# THAPMU__1_0.net
KiCad netlist of a schematic drawn in EAGLE
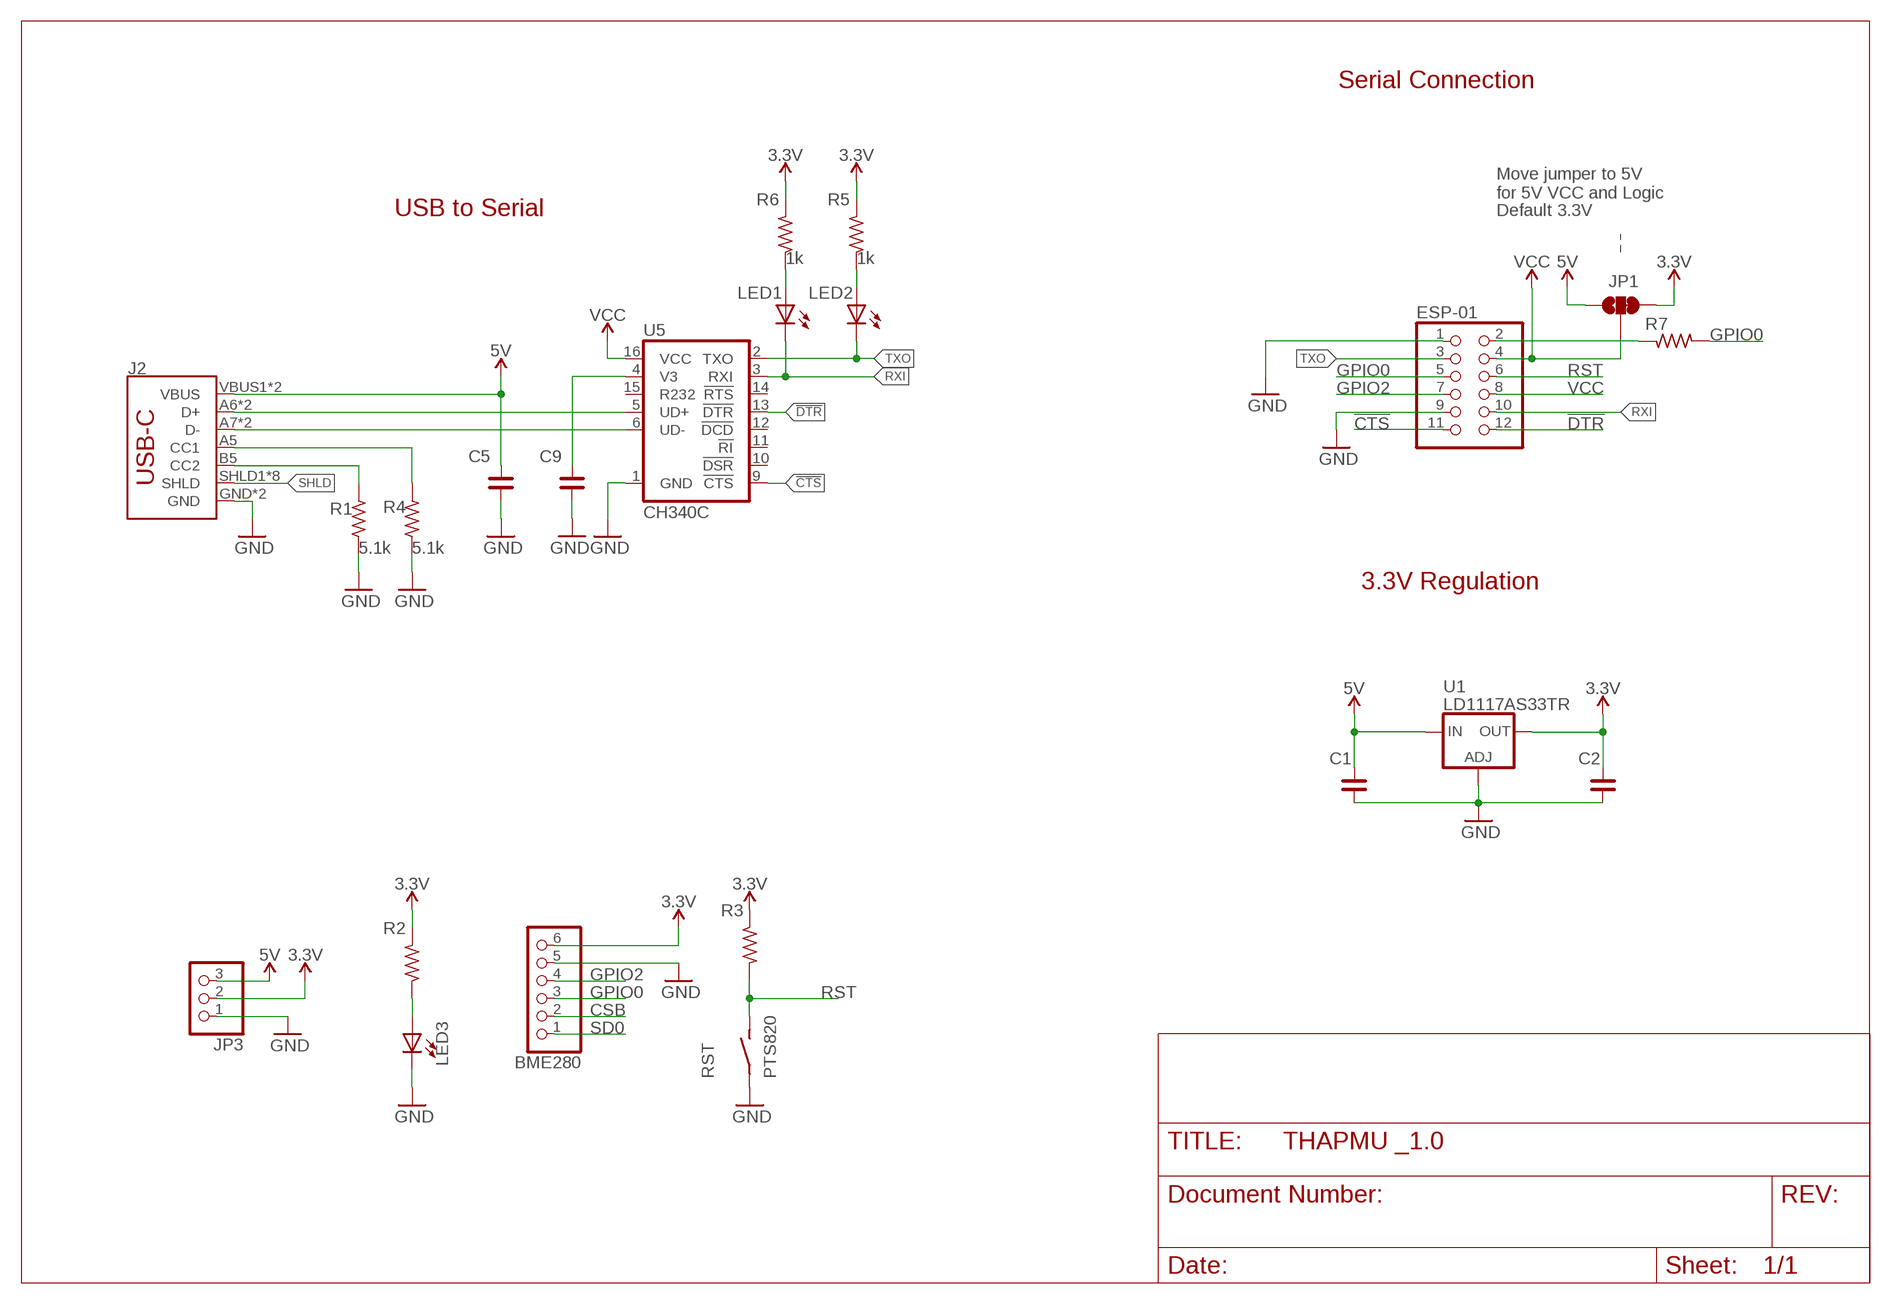
[diagram p0: schematic, sheet 1]

(export (version "E")
  (design (tool "Eeschema 10.0.6"))
  (components
    (comp (ref "BME280")
      (value "PINHD-1X6")
      (footprint "eagle-import:1X06")
      (libsource (lib "eagle-import") (part "PINHD-1X6"))
    )
    (comp (ref "C1")
      (value "0.1uF")
      (footprint "eagle-import:C1206")
      (libsource (lib "eagle-import") (part "C_1206"))
    )
    (comp (ref "C2")
      (value "10uF")
      (footprint "eagle-import:C1206")
      (libsource (lib "eagle-import") (part "C_1206"))
    )
    (comp (ref "C5")
      (value "0.1uF")
      (footprint "eagle-import:C1206")
      (libsource (lib "eagle-import") (part "C_1206"))
    )
    (comp (ref "C9")
      (value "10nF")
      (footprint "eagle-import:C1206")
      (libsource (lib "eagle-import") (part "C_1206"))
    )
    (comp (ref "ESP-01")
      (value "PINHD-2X6")
      (footprint "eagle-import:2X06")
      (libsource (lib "eagle-import") (part "PINHD-2X6"))
    )
    (comp (ref "J2")
      (value "USB_C16PIN")
      (footprint "eagle-import:USB-C-16P")
      (libsource (lib "eagle-import") (part "USB_C16PIN"))
    )
    (comp (ref "JP1")
      (value "JUMPER-SMT_3_1-NC_TRACE_SILK")
      (footprint "eagle-import:SMT-JUMPER_3_1-NC_TRACE_SILK")
      (libsource (lib "eagle-import") (part "JUMPER-SMT_3_1-NC_TRACE_SILK"))
    )
    (comp (ref "JP3")
      (value "PINHD-1X3_2.00")
      (footprint "eagle-import:1X03M")
      (libsource (lib "eagle-import") (part "PINHD-1X3_2.00"))
    )
    (comp (ref "LED1")
      (value "GREEN")
      (footprint "eagle-import:1206")
      (libsource (lib "eagle-import") (part "LEDSMT1206"))
    )
    (comp (ref "LED2")
      (value "Yellow")
      (footprint "eagle-import:1206")
      (libsource (lib "eagle-import") (part "LEDSMT1206"))
    )
    (comp (ref "LED3")
      (value "BLUE")
      (footprint "eagle-import:1206")
      (libsource (lib "eagle-import") (part "LEDSMT1206"))
    )
    (comp (ref "R1")
      (value "5.1k")
      (footprint "eagle-import:R1206")
      (fields (field (name "V") "5.1k"))
      (libsource (lib "eagle-import") (part "R_1206"))
    )
    (comp (ref "R2")
      (value "1k")
      (footprint "eagle-import:R1206")
      (libsource (lib "eagle-import") (part "R_1206"))
    )
    (comp (ref "R3")
      (value "1k")
      (footprint "eagle-import:R1206")
      (libsource (lib "eagle-import") (part "R_1206"))
    )
    (comp (ref "R4")
      (value "5.1k")
      (footprint "eagle-import:R1206")
      (fields (field (name "V") "5.1k"))
      (libsource (lib "eagle-import") (part "R_1206"))
    )
    (comp (ref "R5")
      (value "1k")
      (footprint "eagle-import:R1206")
      (fields (field (name "V") "1k"))
      (libsource (lib "eagle-import") (part "R_1206"))
    )
    (comp (ref "R6")
      (value "1k")
      (footprint "eagle-import:R1206")
      (fields (field (name "V") "1k"))
      (libsource (lib "eagle-import") (part "R_1206"))
    )
    (comp (ref "R7")
      (value "1k")
      (footprint "eagle-import:R1206")
      (libsource (lib "eagle-import") (part "R_1206"))
    )
    (comp (ref "RST")
      (value "PTS820")
      (footprint "eagle-import:PTS820")
      (libsource (lib "eagle-import") (part "PTS820"))
    )
    (comp (ref "U1")
      (value "LD1117AS33TR")
      (footprint "eagle-import:SOT223")
      (libsource (lib "eagle-import") (part "LD117A?S33TR"))
    )
    (comp (ref "U5")
      (value "CH340C")
      (footprint "eagle-import:SO016")
      (libsource (lib "eagle-import") (part "CH340C"))
    )
  )
  (nets
    (net (code "1") (name "/CSB") (class "Default")
      (node (ref "BME280") (pin "2") (pinfunction "2_2") (pintype "passive"))
    )
    (net (code "2") (name "/GPIO0") (class "Default")
      (node (ref "BME280") (pin "3") (pinfunction "3_3") (pintype "passive"))
      (node (ref "ESP-01") (pin "5") (pinfunction "5_5") (pintype "passive"))
      (node (ref "R7") (pin "2") (pinfunction "2_2") (pintype "passive"))
    )
    (net (code "3") (name "/GPIO2") (class "Default")
      (node (ref "BME280") (pin "4") (pinfunction "4_4") (pintype "passive"))
      (node (ref "ESP-01") (pin "7") (pinfunction "7_7") (pintype "passive"))
    )
    (net (code "4") (name "/RST") (class "Default")
      (node (ref "ESP-01") (pin "6") (pinfunction "6_6") (pintype "passive"))
      (node (ref "R3") (pin "1") (pinfunction "1_1") (pintype "passive"))
      (node (ref "RST") (pin "2") (pinfunction "S_2") (pintype "passive"))
    )
    (net (code "5") (name "/SD0") (class "Default")
      (node (ref "BME280") (pin "1") (pinfunction "1_1") (pintype "passive"))
    )
    (net (code "6") (name "/~{CTS}") (class "Default")
      (node (ref "ESP-01") (pin "11") (pinfunction "11_11") (pintype "passive"))
      (node (ref "U5") (pin "9") (pinfunction "~{CTS}_9") (pintype "bidirectional"))
    )
    (net (code "7") (name "/~{DTR}") (class "Default")
      (node (ref "ESP-01") (pin "12") (pinfunction "12_12") (pintype "passive"))
      (node (ref "U5") (pin "13") (pinfunction "~{DTR}_13") (pintype "bidirectional"))
    )
    (net (code "8") (name "3.3V") (class "Default")
      (node (ref "BME280") (pin "6") (pinfunction "6_6") (pintype "passive"))
      (node (ref "C2") (pin "1") (pinfunction "1_1") (pintype "passive"))
      (node (ref "JP1") (pin "3") (pinfunction "3_3") (pintype "passive"))
      (node (ref "JP3") (pin "2") (pinfunction "2_2") (pintype "passive"))
      (node (ref "R2") (pin "2") (pinfunction "2_2") (pintype "passive"))
      (node (ref "R3") (pin "2") (pinfunction "2_2") (pintype "passive"))
      (node (ref "R5") (pin "2") (pinfunction "2_2") (pintype "passive"))
      (node (ref "R6") (pin "2") (pinfunction "2_2") (pintype "passive"))
      (node (ref "U1") (pin "4") (pinfunction "OUT_4") (pintype "passive"))
    )
    (net (code "9") (name "5V") (class "Default")
      (node (ref "C1") (pin "1") (pinfunction "1_1") (pintype "passive"))
      (node (ref "C5") (pin "1") (pinfunction "1_1") (pintype "passive"))
      (node (ref "J2") (pin "VBUS1") (pinfunction "VBUS_VBUS1") (pintype "bidirectional"))
      (node (ref "J2") (pin "VBUS2") (pinfunction "VBUS_VBUS2") (pintype "bidirectional"))
      (node (ref "JP1") (pin "1") (pinfunction "1_1") (pintype "passive"))
      (node (ref "JP3") (pin "3") (pinfunction "3_3") (pintype "passive"))
      (node (ref "U1") (pin "3") (pinfunction "IN_3") (pintype "input"))
    )
    (net (code "10") (name "GND") (class "Default")
      (node (ref "BME280") (pin "5") (pinfunction "5_5") (pintype "passive"))
      (node (ref "C1") (pin "2") (pinfunction "2_2") (pintype "passive"))
      (node (ref "C2") (pin "2") (pinfunction "2_2") (pintype "passive"))
      (node (ref "C5") (pin "2") (pinfunction "2_2") (pintype "passive"))
      (node (ref "C9") (pin "2") (pinfunction "2_2") (pintype "passive"))
      (node (ref "ESP-01") (pin "1") (pinfunction "1_1") (pintype "passive"))
      (node (ref "ESP-01") (pin "9") (pinfunction "9_9") (pintype "passive"))
      (node (ref "J2") (pin "GND") (pinfunction "GND_GND") (pintype "bidirectional"))
      (node (ref "J2") (pin "GND2") (pinfunction "GND_GND2") (pintype "bidirectional"))
      (node (ref "JP3") (pin "1") (pinfunction "1_1") (pintype "passive"))
      (node (ref "LED3") (pin "C") (pinfunction "C_C") (pintype "passive"))
      (node (ref "R1") (pin "1") (pinfunction "1_1") (pintype "passive"))
      (node (ref "R4") (pin "1") (pinfunction "1_1") (pintype "passive"))
      (node (ref "RST") (pin "1") (pinfunction "P_1") (pintype "passive"))
      (node (ref "U1") (pin "1") (pinfunction "ADJ_1") (pintype "input"))
      (node (ref "U5") (pin "1") (pinfunction "GND_1") (pintype "bidirectional"))
    )
    (net (code "11") (name "Net-(ESP-01-Pad2)") (class "Default")
      (node (ref "ESP-01") (pin "2") (pinfunction "2_2") (pintype "passive"))
      (node (ref "R7") (pin "1") (pinfunction "1_1") (pintype "passive"))
    )
    (net (code "12") (name "Net-(J2-CC1)") (class "Default")
      (node (ref "J2") (pin "A5") (pinfunction "CC1_A5") (pintype "bidirectional"))
      (node (ref "R4") (pin "2") (pinfunction "2_2") (pintype "passive"))
    )
    (net (code "13") (name "Net-(J2-CC2)") (class "Default")
      (node (ref "J2") (pin "B5") (pinfunction "CC2_B5") (pintype "bidirectional"))
      (node (ref "R1") (pin "2") (pinfunction "2_2") (pintype "passive"))
    )
    (net (code "14") (name "Net-(LED1-PadA)") (class "Default")
      (node (ref "LED1") (pin "A") (pinfunction "A_A") (pintype "passive"))
      (node (ref "R6") (pin "1") (pinfunction "1_1") (pintype "passive"))
    )
    (net (code "15") (name "Net-(LED2-PadA)") (class "Default")
      (node (ref "LED2") (pin "A") (pinfunction "A_A") (pintype "passive"))
      (node (ref "R5") (pin "1") (pinfunction "1_1") (pintype "passive"))
    )
    (net (code "16") (name "Net-(LED3-PadA)") (class "Default")
      (node (ref "LED3") (pin "A") (pinfunction "A_A") (pintype "passive"))
      (node (ref "R2") (pin "1") (pinfunction "1_1") (pintype "passive"))
    )
    (net (code "17") (name "Net-(U5-UD+)") (class "Default")
      (node (ref "J2") (pin "A6") (pinfunction "D+_A6") (pintype "bidirectional"))
      (node (ref "J2") (pin "B6") (pinfunction "D+_B6") (pintype "bidirectional"))
      (node (ref "U5") (pin "5") (pinfunction "UD+_5") (pintype "bidirectional"))
    )
    (net (code "18") (name "Net-(U5-UD-)") (class "Default")
      (node (ref "J2") (pin "A7") (pinfunction "D-_A7") (pintype "bidirectional"))
      (node (ref "J2") (pin "B7") (pinfunction "D-_B7") (pintype "bidirectional"))
      (node (ref "U5") (pin "6") (pinfunction "UD-_6") (pintype "bidirectional"))
    )
    (net (code "19") (name "Net-(U5-V3)") (class "Default")
      (node (ref "C9") (pin "1") (pinfunction "1_1") (pintype "passive"))
      (node (ref "U5") (pin "4") (pinfunction "V3_4") (pintype "bidirectional"))
    )
    (net (code "20") (name "RXI") (class "Default")
      (node (ref "ESP-01") (pin "10") (pinfunction "10_10") (pintype "passive"))
      (node (ref "LED1") (pin "C") (pinfunction "C_C") (pintype "passive"))
      (node (ref "U5") (pin "3") (pinfunction "RXI_3") (pintype "bidirectional"))
    )
    (net (code "21") (name "SHLD") (class "Default")
      (node (ref "J2") (pin "SHLD1") (pinfunction "SHLD_SHLD1") (pintype "bidirectional"))
      (node (ref "J2") (pin "SHLD2") (pinfunction "SHLD_SHLD2") (pintype "bidirectional"))
      (node (ref "J2") (pin "SHLD3") (pinfunction "SHLD_SHLD3") (pintype "bidirectional"))
      (node (ref "J2") (pin "SHLD4") (pinfunction "SHLD_SHLD4") (pintype "bidirectional"))
      (node (ref "J2") (pin "SHLD5") (pinfunction "SHLD_SHLD5") (pintype "bidirectional"))
      (node (ref "J2") (pin "SHLD6") (pinfunction "SHLD_SHLD6") (pintype "bidirectional"))
      (node (ref "J2") (pin "SHLD7") (pinfunction "SHLD_SHLD7") (pintype "bidirectional"))
      (node (ref "J2") (pin "SHLD8") (pinfunction "SHLD_SHLD8") (pintype "bidirectional"))
    )
    (net (code "22") (name "TXO") (class "Default")
      (node (ref "ESP-01") (pin "3") (pinfunction "3_3") (pintype "passive"))
      (node (ref "LED2") (pin "C") (pinfunction "C_C") (pintype "passive"))
      (node (ref "U5") (pin "2") (pinfunction "TXO_2") (pintype "bidirectional"))
    )
    (net (code "23") (name "VCC") (class "Default")
      (node (ref "ESP-01") (pin "4") (pinfunction "4_4") (pintype "passive"))
      (node (ref "ESP-01") (pin "8") (pinfunction "8_8") (pintype "passive"))
      (node (ref "JP1") (pin "2") (pinfunction "2_2") (pintype "passive"))
      (node (ref "U5") (pin "16") (pinfunction "VCC_16") (pintype "bidirectional"))
    )
    (net (code "24") (name "unconnected-(U5-R232-Pad15)") (class "Default")
      (node (ref "U5") (pin "15") (pinfunction "R232_15") (pintype "bidirectional"))
    )
    (net (code "25") (name "unconnected-(U5-~{DCD}-Pad12)") (class "Default")
      (node (ref "U5") (pin "12") (pinfunction "~{DCD}_12") (pintype "bidirectional"))
    )
    (net (code "26") (name "unconnected-(U5-~{DSR}-Pad10)") (class "Default")
      (node (ref "U5") (pin "10") (pinfunction "~{DSR}_10") (pintype "bidirectional"))
    )
    (net (code "27") (name "unconnected-(U5-~{RI}-Pad11)") (class "Default")
      (node (ref "U5") (pin "11") (pinfunction "~{RI}_11") (pintype "bidirectional"))
    )
    (net (code "28") (name "unconnected-(U5-~{RTS}-Pad14)") (class "Default")
      (node (ref "U5") (pin "14") (pinfunction "~{RTS}_14") (pintype "bidirectional"))
    )
  )
)
